# SCH_HomeControl_2022-04-17.net
KiCad netlist of a schematic drawn in EasyEDA
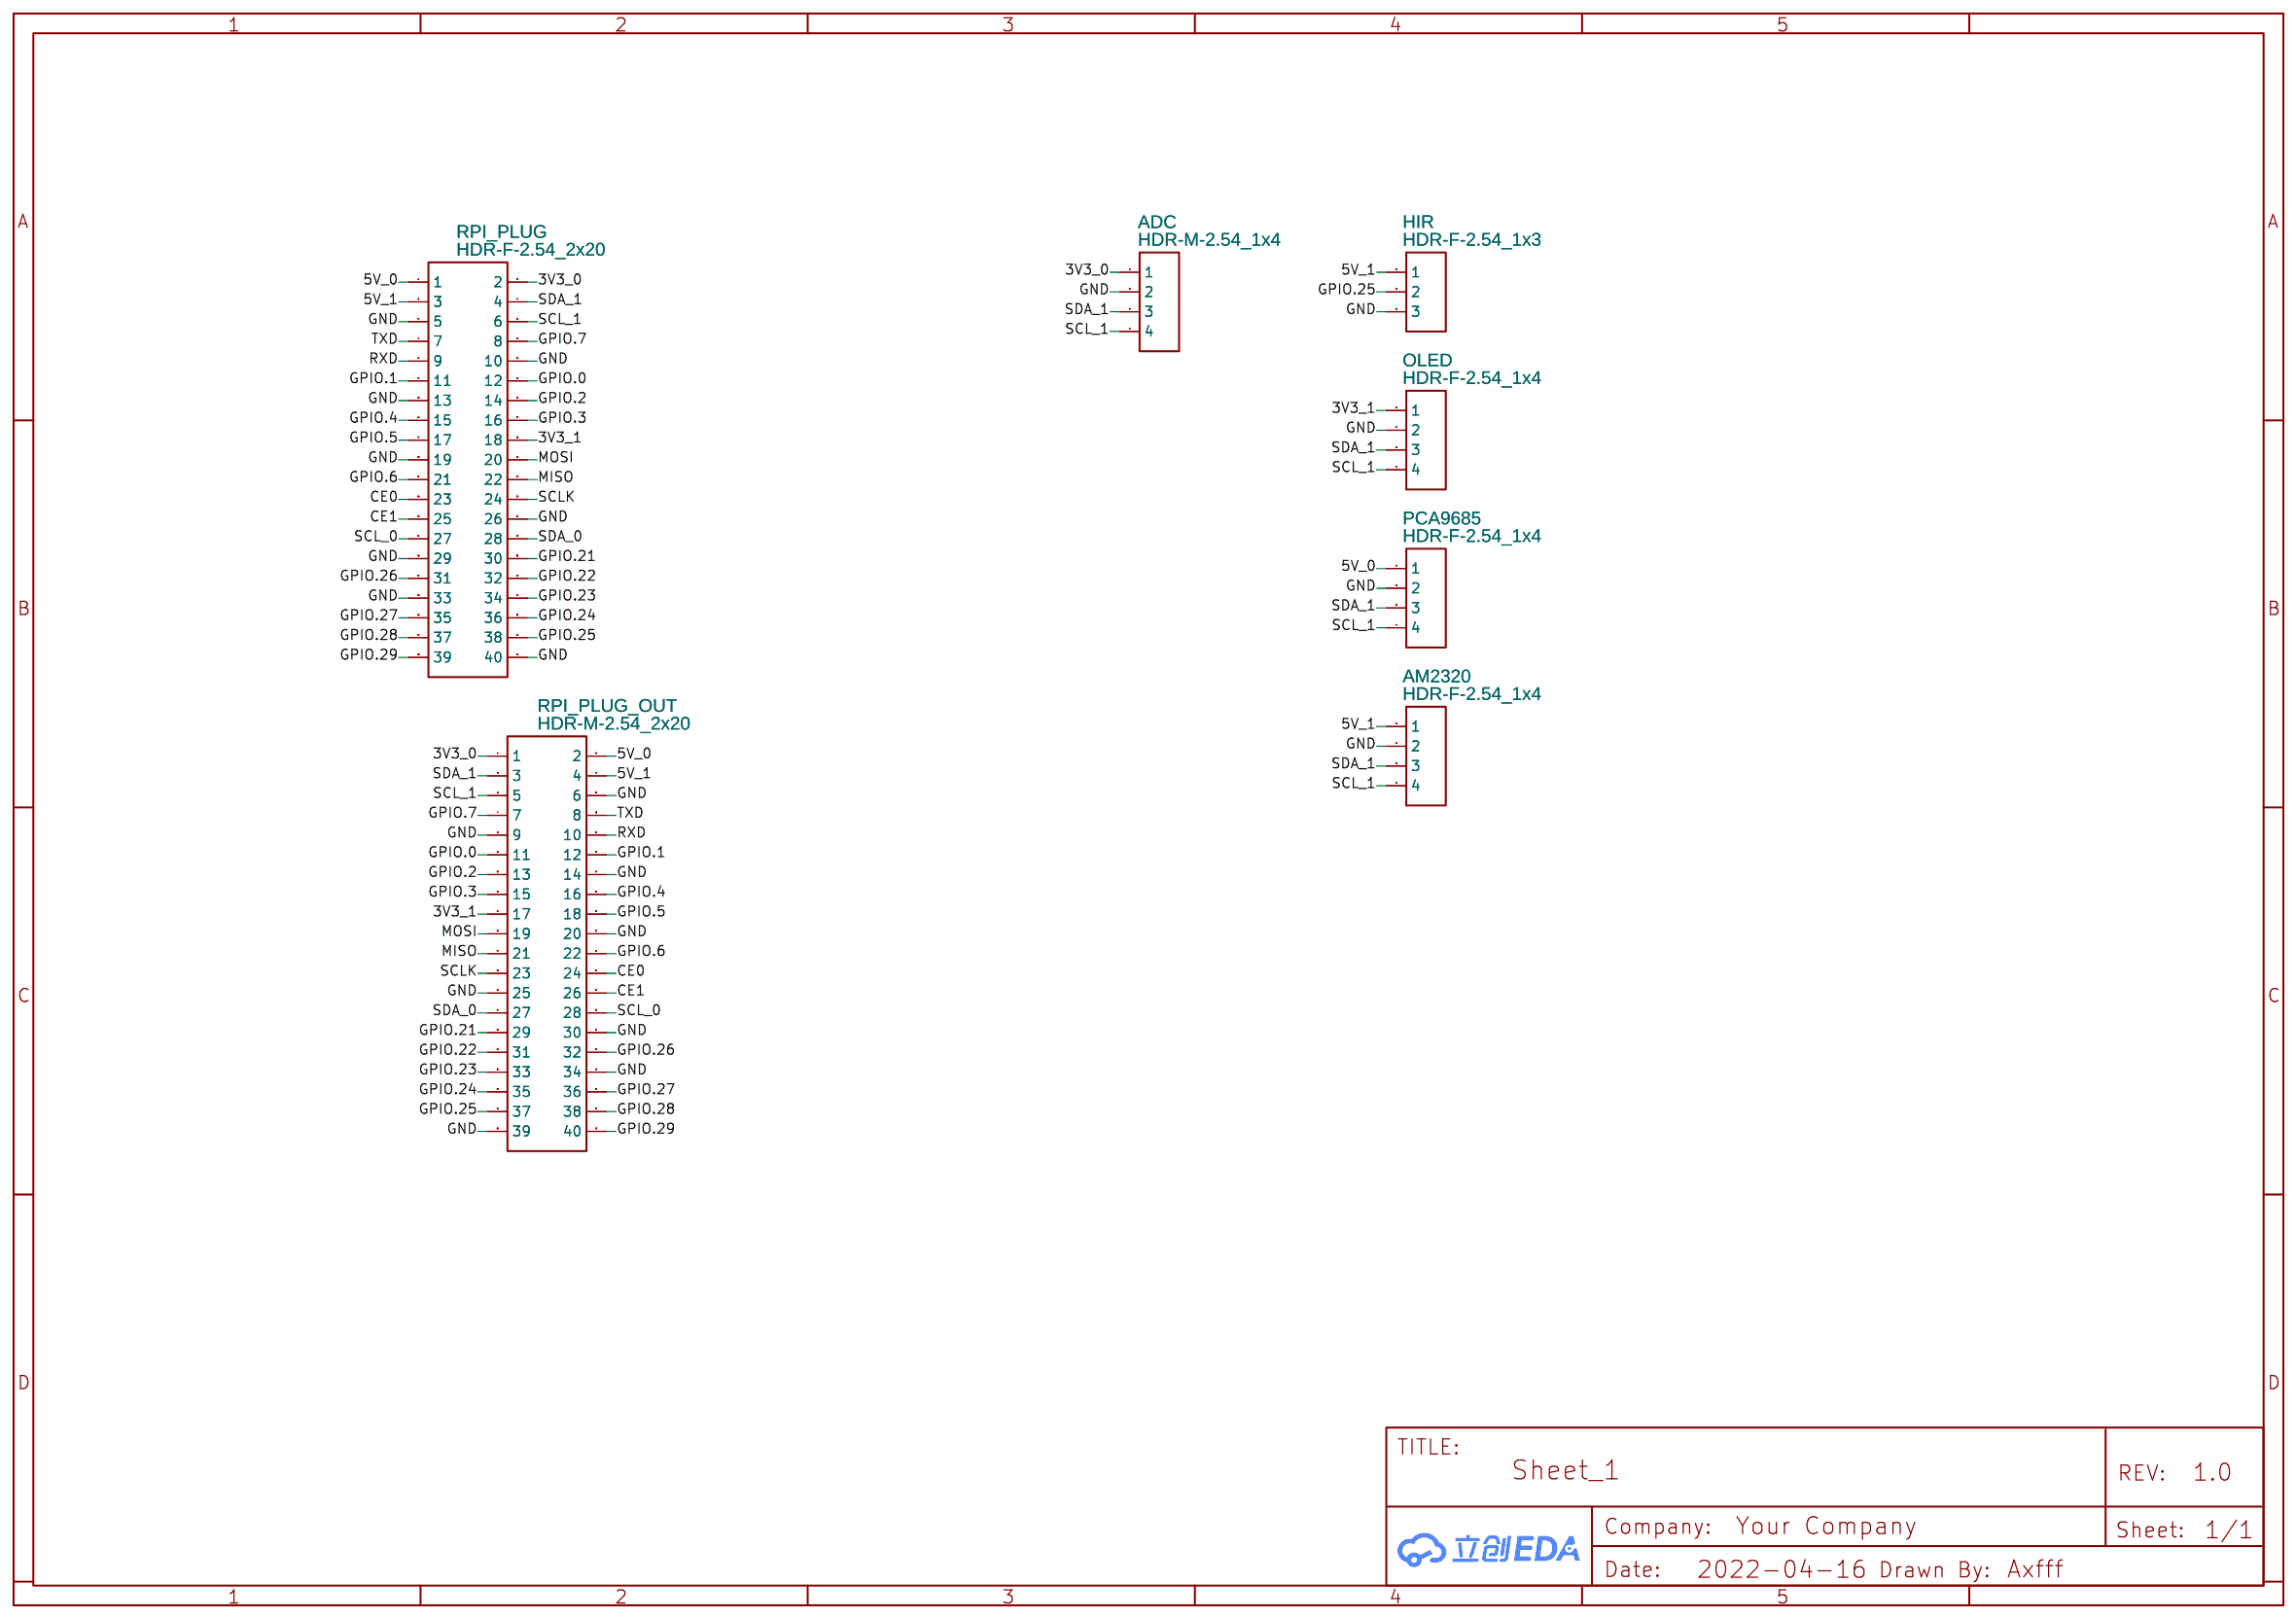
[diagram p0: schematic sheet]

(export (version "E")
  (design (tool "Eeschema 10.0.6"))
  (components
    (comp (ref "ADC")
      (value "HDR-M-2.54_1x4")
      (fields (field (name "BOM_Supplier Part") "C124378"))
      (libsource (lib "") (part "HDR-M-2.54_1x4"))
    )
    (comp (ref "AM2320")
      (value "HDR-F-2.54_1x4")
      (fields (field (name "BOM_Supplier Part") "C225501"))
      (libsource (lib "") (part "HDR-F-2.54_1x4_1"))
    )
    (comp (ref "HIR")
      (value "HDR-F-2.54_1x3")
      (fields (field (name "BOM_Supplier Part") "C146690"))
      (libsource (lib "") (part "HDR-F-2.54_1x3"))
    )
    (comp (ref "OLED")
      (value "HDR-F-2.54_1x4")
      (fields (field (name "BOM_Supplier Part") "C225501"))
      (libsource (lib "") (part "HDR-F-2.54_1x4"))
    )
    (comp (ref "PCA9685")
      (value "HDR-F-2.54_1x4")
      (fields (field (name "BOM_Supplier Part") "C225501"))
      (libsource (lib "") (part "HDR-F-2.54_1x4_2"))
    )
    (comp (ref "RPI_PLUG")
      (value "HDR-F-2.54_2x20")
      (fields (field (name "BOM_Supplier Part") "C50982"))
      (libsource (lib "") (part "HDR-F-2.54_2x20"))
    )
    (comp (ref "RPI_PLUG_OUT")
      (value "HDR-M-2.54_2x20")
      (fields (field (name "BOM_Supplier Part") "C50980"))
      (libsource (lib "") (part "HDR-M-2.54_2x20"))
    )
  )
  (nets
    (net (code "1") (name "/3V3_0") (class "Default")
      (node (ref "ADC") (pin "1") (pinfunction "1_1") (pintype "unspecified"))
      (node (ref "RPI_PLUG") (pin "2") (pinfunction "2_2") (pintype "input"))
      (node (ref "RPI_PLUG_OUT") (pin "1") (pinfunction "1_1") (pintype "input"))
    )
    (net (code "2") (name "/3V3_1") (class "Default")
      (node (ref "OLED") (pin "1") (pinfunction "1_1") (pintype "unspecified"))
      (node (ref "RPI_PLUG") (pin "18") (pinfunction "18_18") (pintype "input"))
      (node (ref "RPI_PLUG_OUT") (pin "17") (pinfunction "17_17") (pintype "input"))
    )
    (net (code "3") (name "/5V_0") (class "Default")
      (node (ref "PCA9685") (pin "1") (pinfunction "1_1") (pintype "unspecified"))
      (node (ref "RPI_PLUG") (pin "1") (pinfunction "1_1") (pintype "input"))
      (node (ref "RPI_PLUG_OUT") (pin "2") (pinfunction "2_2") (pintype "input"))
    )
    (net (code "4") (name "/5V_1") (class "Default")
      (node (ref "AM2320") (pin "1") (pinfunction "1_1") (pintype "unspecified"))
      (node (ref "HIR") (pin "1") (pinfunction "1_1") (pintype "input"))
      (node (ref "RPI_PLUG") (pin "3") (pinfunction "3_3") (pintype "input"))
      (node (ref "RPI_PLUG_OUT") (pin "4") (pinfunction "4_4") (pintype "input"))
    )
    (net (code "5") (name "/CE0") (class "Default")
      (node (ref "RPI_PLUG") (pin "23") (pinfunction "23_23") (pintype "input"))
      (node (ref "RPI_PLUG_OUT") (pin "24") (pinfunction "24_24") (pintype "input"))
    )
    (net (code "6") (name "/CE1") (class "Default")
      (node (ref "RPI_PLUG") (pin "25") (pinfunction "25_25") (pintype "input"))
      (node (ref "RPI_PLUG_OUT") (pin "26") (pinfunction "26_26") (pintype "input"))
    )
    (net (code "7") (name "/GND") (class "Default")
      (node (ref "ADC") (pin "2") (pinfunction "2_2") (pintype "unspecified"))
      (node (ref "AM2320") (pin "2") (pinfunction "2_2") (pintype "unspecified"))
      (node (ref "HIR") (pin "3") (pinfunction "3_3") (pintype "input"))
      (node (ref "OLED") (pin "2") (pinfunction "2_2") (pintype "unspecified"))
      (node (ref "PCA9685") (pin "2") (pinfunction "2_2") (pintype "unspecified"))
      (node (ref "RPI_PLUG") (pin "10") (pinfunction "10_10") (pintype "input"))
      (node (ref "RPI_PLUG") (pin "13") (pinfunction "13_13") (pintype "input"))
      (node (ref "RPI_PLUG") (pin "19") (pinfunction "19_19") (pintype "input"))
      (node (ref "RPI_PLUG") (pin "26") (pinfunction "26_26") (pintype "input"))
      (node (ref "RPI_PLUG") (pin "29") (pinfunction "29_29") (pintype "input"))
      (node (ref "RPI_PLUG") (pin "33") (pinfunction "33_33") (pintype "input"))
      (node (ref "RPI_PLUG") (pin "40") (pinfunction "40_40") (pintype "input"))
      (node (ref "RPI_PLUG") (pin "5") (pinfunction "5_5") (pintype "input"))
      (node (ref "RPI_PLUG_OUT") (pin "14") (pinfunction "14_14") (pintype "input"))
      (node (ref "RPI_PLUG_OUT") (pin "20") (pinfunction "20_20") (pintype "input"))
      (node (ref "RPI_PLUG_OUT") (pin "25") (pinfunction "25_25") (pintype "input"))
      (node (ref "RPI_PLUG_OUT") (pin "30") (pinfunction "30_30") (pintype "input"))
      (node (ref "RPI_PLUG_OUT") (pin "34") (pinfunction "34_34") (pintype "input"))
      (node (ref "RPI_PLUG_OUT") (pin "39") (pinfunction "39_39") (pintype "input"))
      (node (ref "RPI_PLUG_OUT") (pin "6") (pinfunction "6_6") (pintype "input"))
      (node (ref "RPI_PLUG_OUT") (pin "9") (pinfunction "9_9") (pintype "input"))
    )
    (net (code "8") (name "/GPIO.0") (class "Default")
      (node (ref "RPI_PLUG") (pin "12") (pinfunction "12_12") (pintype "input"))
      (node (ref "RPI_PLUG_OUT") (pin "11") (pinfunction "11_11") (pintype "input"))
    )
    (net (code "9") (name "/GPIO.1") (class "Default")
      (node (ref "RPI_PLUG") (pin "11") (pinfunction "11_11") (pintype "input"))
      (node (ref "RPI_PLUG_OUT") (pin "12") (pinfunction "12_12") (pintype "input"))
    )
    (net (code "10") (name "/GPIO.2") (class "Default")
      (node (ref "RPI_PLUG") (pin "14") (pinfunction "14_14") (pintype "input"))
      (node (ref "RPI_PLUG_OUT") (pin "13") (pinfunction "13_13") (pintype "input"))
    )
    (net (code "11") (name "/GPIO.3") (class "Default")
      (node (ref "RPI_PLUG") (pin "16") (pinfunction "16_16") (pintype "input"))
      (node (ref "RPI_PLUG_OUT") (pin "15") (pinfunction "15_15") (pintype "input"))
    )
    (net (code "12") (name "/GPIO.4") (class "Default")
      (node (ref "RPI_PLUG") (pin "15") (pinfunction "15_15") (pintype "input"))
      (node (ref "RPI_PLUG_OUT") (pin "16") (pinfunction "16_16") (pintype "input"))
    )
    (net (code "13") (name "/GPIO.5") (class "Default")
      (node (ref "RPI_PLUG") (pin "17") (pinfunction "17_17") (pintype "input"))
      (node (ref "RPI_PLUG_OUT") (pin "18") (pinfunction "18_18") (pintype "input"))
    )
    (net (code "14") (name "/GPIO.6") (class "Default")
      (node (ref "RPI_PLUG") (pin "21") (pinfunction "21_21") (pintype "input"))
      (node (ref "RPI_PLUG_OUT") (pin "22") (pinfunction "22_22") (pintype "input"))
    )
    (net (code "15") (name "/GPIO.7") (class "Default")
      (node (ref "RPI_PLUG") (pin "8") (pinfunction "8_8") (pintype "input"))
      (node (ref "RPI_PLUG_OUT") (pin "7") (pinfunction "7_7") (pintype "input"))
    )
    (net (code "16") (name "/GPIO.21") (class "Default")
      (node (ref "RPI_PLUG") (pin "30") (pinfunction "30_30") (pintype "input"))
      (node (ref "RPI_PLUG_OUT") (pin "29") (pinfunction "29_29") (pintype "input"))
    )
    (net (code "17") (name "/GPIO.22") (class "Default")
      (node (ref "RPI_PLUG") (pin "32") (pinfunction "32_32") (pintype "input"))
      (node (ref "RPI_PLUG_OUT") (pin "31") (pinfunction "31_31") (pintype "input"))
    )
    (net (code "18") (name "/GPIO.23") (class "Default")
      (node (ref "RPI_PLUG") (pin "34") (pinfunction "34_34") (pintype "input"))
      (node (ref "RPI_PLUG_OUT") (pin "33") (pinfunction "33_33") (pintype "input"))
    )
    (net (code "19") (name "/GPIO.24") (class "Default")
      (node (ref "RPI_PLUG") (pin "36") (pinfunction "36_36") (pintype "input"))
      (node (ref "RPI_PLUG_OUT") (pin "35") (pinfunction "35_35") (pintype "input"))
    )
    (net (code "20") (name "/GPIO.25") (class "Default")
      (node (ref "HIR") (pin "2") (pinfunction "2_2") (pintype "input"))
      (node (ref "RPI_PLUG") (pin "38") (pinfunction "38_38") (pintype "input"))
      (node (ref "RPI_PLUG_OUT") (pin "37") (pinfunction "37_37") (pintype "input"))
    )
    (net (code "21") (name "/GPIO.26") (class "Default")
      (node (ref "RPI_PLUG") (pin "31") (pinfunction "31_31") (pintype "input"))
      (node (ref "RPI_PLUG_OUT") (pin "32") (pinfunction "32_32") (pintype "input"))
    )
    (net (code "22") (name "/GPIO.27") (class "Default")
      (node (ref "RPI_PLUG") (pin "35") (pinfunction "35_35") (pintype "input"))
      (node (ref "RPI_PLUG_OUT") (pin "36") (pinfunction "36_36") (pintype "input"))
    )
    (net (code "23") (name "/GPIO.28") (class "Default")
      (node (ref "RPI_PLUG") (pin "37") (pinfunction "37_37") (pintype "input"))
      (node (ref "RPI_PLUG_OUT") (pin "38") (pinfunction "38_38") (pintype "input"))
    )
    (net (code "24") (name "/GPIO.29") (class "Default")
      (node (ref "RPI_PLUG") (pin "39") (pinfunction "39_39") (pintype "input"))
      (node (ref "RPI_PLUG_OUT") (pin "40") (pinfunction "40_40") (pintype "input"))
    )
    (net (code "25") (name "/MISO") (class "Default")
      (node (ref "RPI_PLUG") (pin "22") (pinfunction "22_22") (pintype "input"))
      (node (ref "RPI_PLUG_OUT") (pin "21") (pinfunction "21_21") (pintype "input"))
    )
    (net (code "26") (name "/MOSI") (class "Default")
      (node (ref "RPI_PLUG") (pin "20") (pinfunction "20_20") (pintype "input"))
      (node (ref "RPI_PLUG_OUT") (pin "19") (pinfunction "19_19") (pintype "input"))
    )
    (net (code "27") (name "/RXD") (class "Default")
      (node (ref "RPI_PLUG") (pin "9") (pinfunction "9_9") (pintype "input"))
      (node (ref "RPI_PLUG_OUT") (pin "10") (pinfunction "10_10") (pintype "input"))
    )
    (net (code "28") (name "/SCLK") (class "Default")
      (node (ref "RPI_PLUG") (pin "24") (pinfunction "24_24") (pintype "input"))
      (node (ref "RPI_PLUG_OUT") (pin "23") (pinfunction "23_23") (pintype "input"))
    )
    (net (code "29") (name "/SCL_0") (class "Default")
      (node (ref "RPI_PLUG") (pin "27") (pinfunction "27_27") (pintype "input"))
      (node (ref "RPI_PLUG_OUT") (pin "28") (pinfunction "28_28") (pintype "input"))
    )
    (net (code "30") (name "/SCL_1") (class "Default")
      (node (ref "ADC") (pin "4") (pinfunction "4_4") (pintype "unspecified"))
      (node (ref "AM2320") (pin "4") (pinfunction "4_4") (pintype "unspecified"))
      (node (ref "OLED") (pin "4") (pinfunction "4_4") (pintype "unspecified"))
      (node (ref "PCA9685") (pin "4") (pinfunction "4_4") (pintype "unspecified"))
      (node (ref "RPI_PLUG") (pin "6") (pinfunction "6_6") (pintype "input"))
      (node (ref "RPI_PLUG_OUT") (pin "5") (pinfunction "5_5") (pintype "input"))
    )
    (net (code "31") (name "/SDA_0") (class "Default")
      (node (ref "RPI_PLUG") (pin "28") (pinfunction "28_28") (pintype "input"))
      (node (ref "RPI_PLUG_OUT") (pin "27") (pinfunction "27_27") (pintype "input"))
    )
    (net (code "32") (name "/SDA_1") (class "Default")
      (node (ref "ADC") (pin "3") (pinfunction "3_3") (pintype "unspecified"))
      (node (ref "AM2320") (pin "3") (pinfunction "3_3") (pintype "unspecified"))
      (node (ref "OLED") (pin "3") (pinfunction "3_3") (pintype "unspecified"))
      (node (ref "PCA9685") (pin "3") (pinfunction "3_3") (pintype "unspecified"))
      (node (ref "RPI_PLUG") (pin "4") (pinfunction "4_4") (pintype "input"))
      (node (ref "RPI_PLUG_OUT") (pin "3") (pinfunction "3_3") (pintype "input"))
    )
    (net (code "33") (name "/TXD") (class "Default")
      (node (ref "RPI_PLUG") (pin "7") (pinfunction "7_7") (pintype "input"))
      (node (ref "RPI_PLUG_OUT") (pin "8") (pinfunction "8_8") (pintype "input"))
    )
  )
)
